# XMOS_chip.net
KiCad netlist of a schematic drawn in Altium Designer
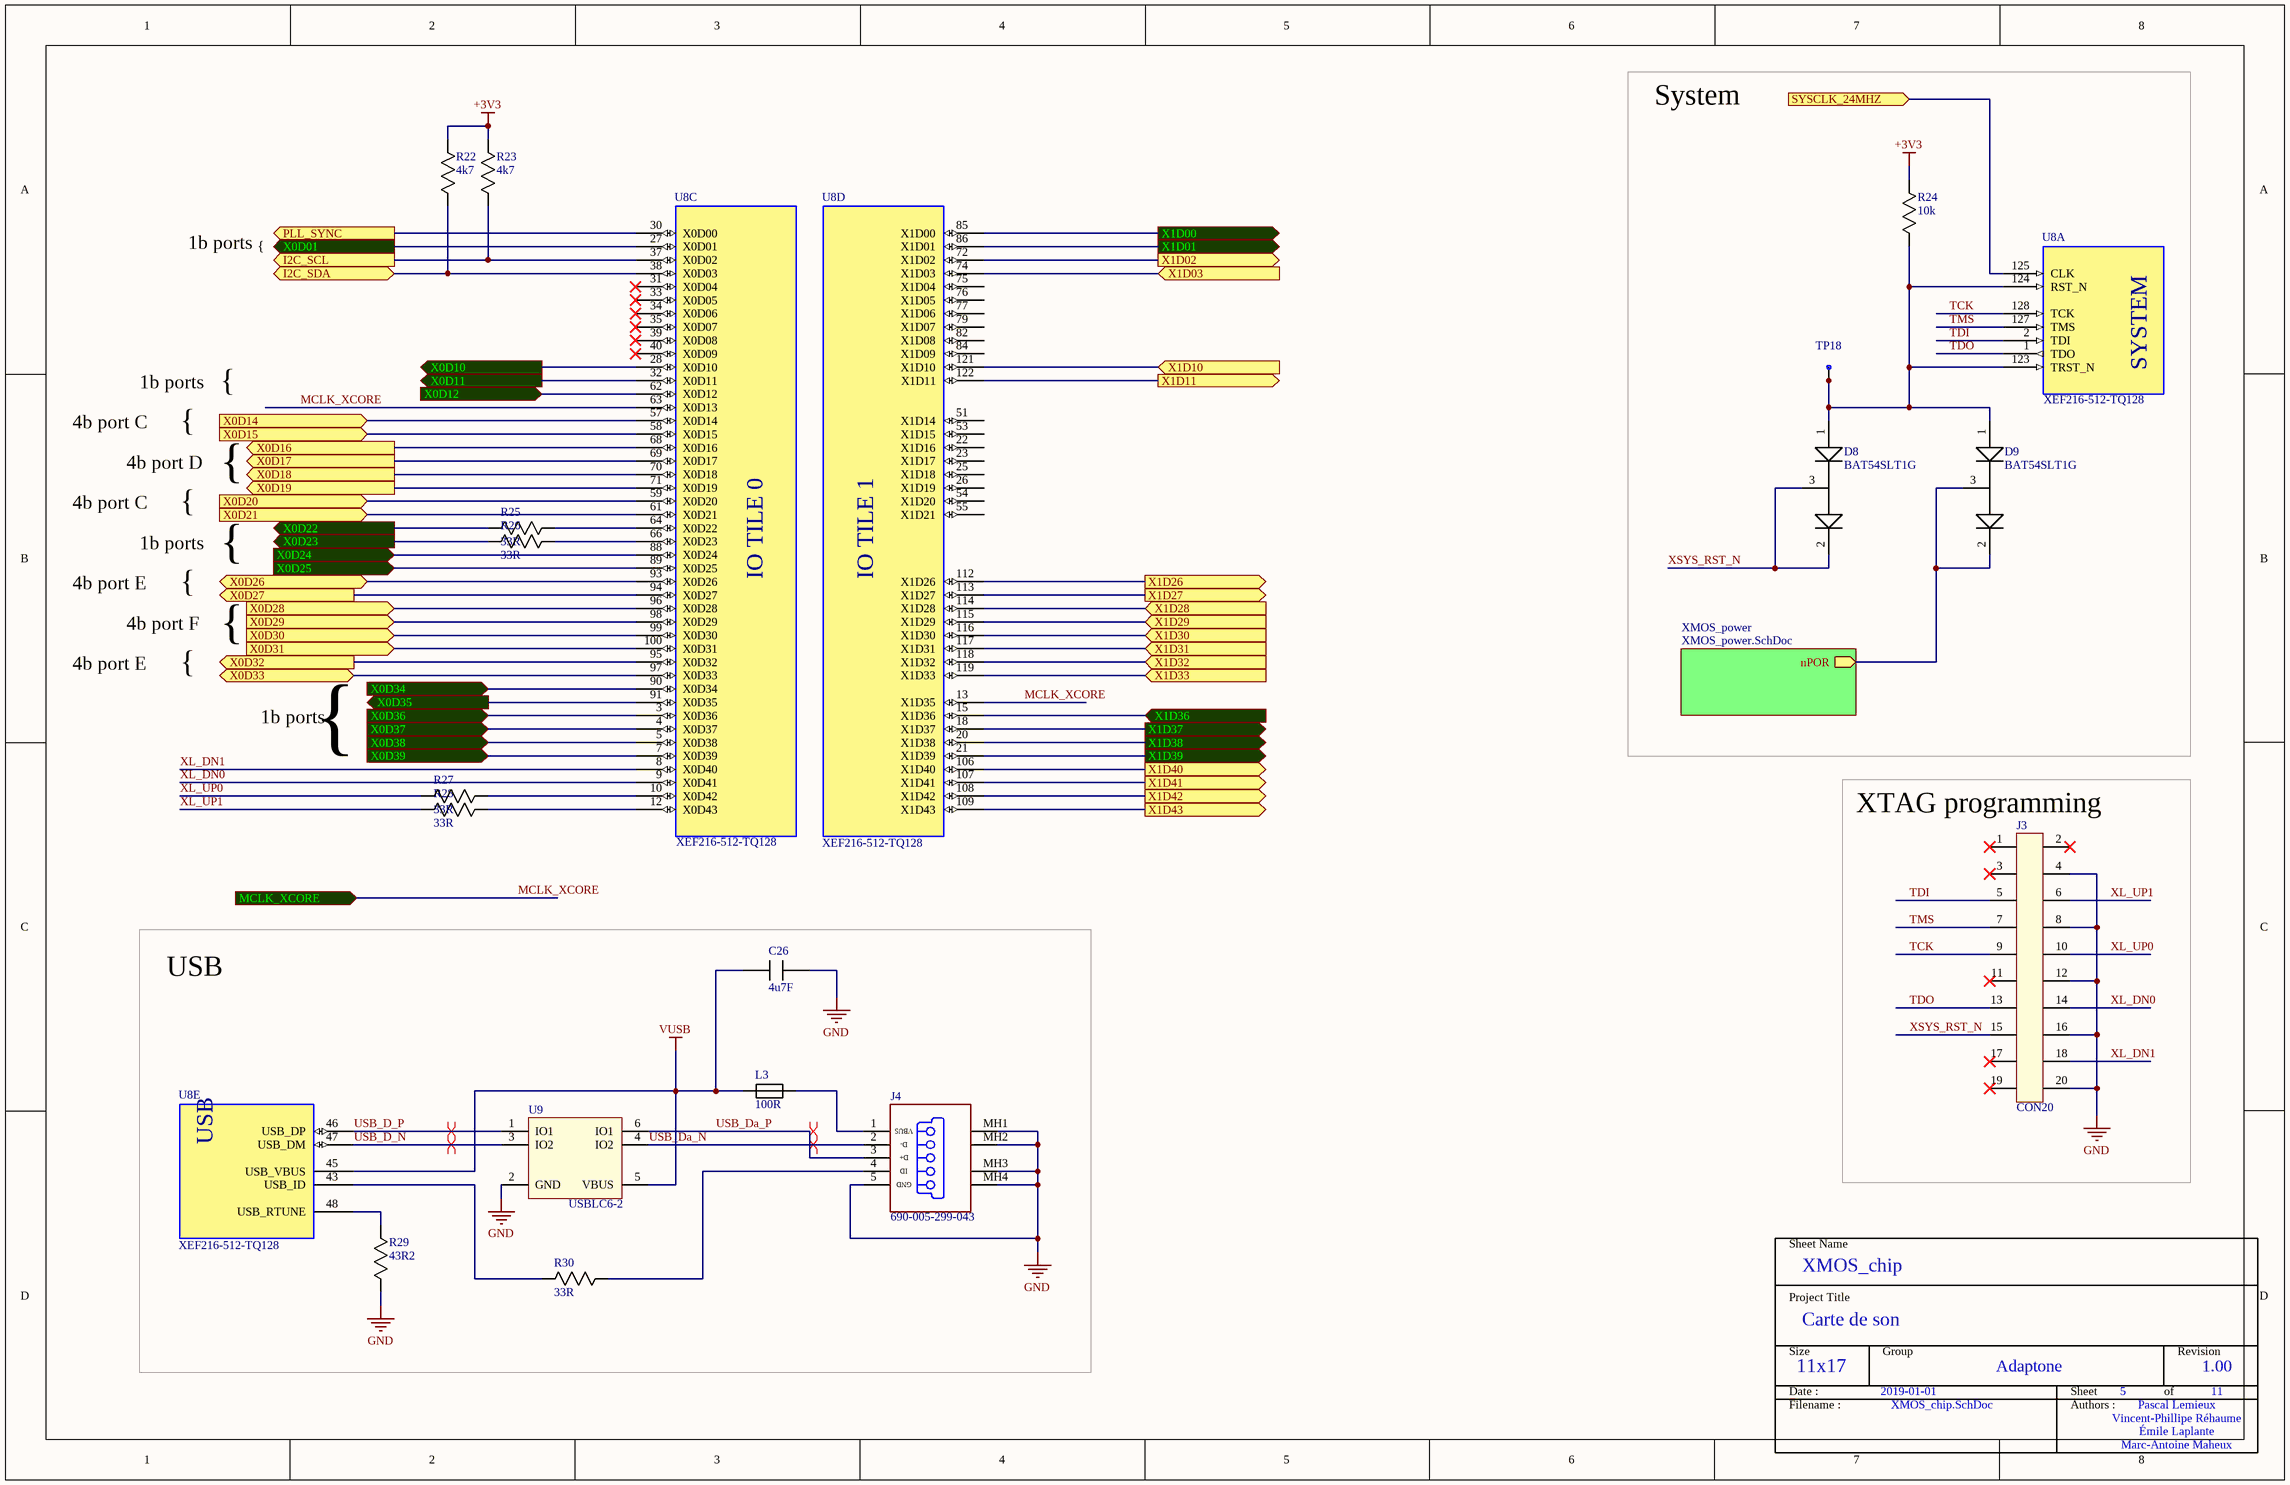
[diagram p0: XMOS_chip.SchDoc]

(export (version "E")
  (design (tool "Eeschema 10.0.6"))
  (components
    (comp (ref "C26")
      (value "4u7F")
      (footprint "0603")
      (description "Capacitor")
      (fields (field (name "MFG") "Samsung"))
      (libsource (lib "ADAPTONE_CARTE_DE_SON") (part "Capacitor"))
    )
    (comp (ref "D8")
      (value "Diode_dual")
      (footprint "SOT23_132")
      (description "Diode")
      (fields (field (name "MFG") "Onsemi") (field (name "MFG_PN") "BAT54SLT1G"))
      (libsource (lib "ADAPTONE_CARTE_DE_SON") (part "Diode_dual"))
    )
    (comp (ref "D9")
      (value "Diode_dual")
      (footprint "SOT23_132")
      (description "Diode")
      (fields (field (name "MFG") "Onsemi") (field (name "MFG_PN") "BAT54SLT1G"))
      (libsource (lib "ADAPTONE_CARTE_DE_SON") (part "Diode_dual"))
    )
    (comp (ref "J3")
      (value "CON20")
      (footprint "CONN20_100mils_pol_SMD")
      (description "20-pins")
      (fields (field (name "MFG") "CNC Tech"))
      (libsource (lib "ADAPTONE_CARTE_DE_SON") (part "CON20"))
    )
    (comp (ref "J4")
      (value "USB_MINIB_690-005-299-043")
      (footprint "CONN_USB_MINIB_690-005-299-043")
      (fields (field (name "MFG") "EDAC") (field (name "MFG_PN") "690-005-299-043"))
      (libsource (lib "ADAPTONE_CARTE_DE_SON") (part "USB_MINIB_690-005-299-043"))
    )
    (comp (ref "L3")
      (value "100R")
      (footprint "0805")
      (description "Ferrite")
      (fields (field (name "MFG") "Bourns"))
      (libsource (lib "ADAPTONE_CARTE_DE_SON") (part "Ferrite"))
    )
    (comp (ref "R22")
      (value "4k7")
      (footprint "0603")
      (description "Resistor")
      (fields (field (name "MFG") "Yageo"))
      (libsource (lib "ADAPTONE_CARTE_DE_SON") (part "Resistor"))
    )
    (comp (ref "R23")
      (value "4k7")
      (footprint "0603")
      (description "Resistor")
      (fields (field (name "MFG") "Yageo"))
      (libsource (lib "ADAPTONE_CARTE_DE_SON") (part "Resistor"))
    )
    (comp (ref "R24")
      (value "10k")
      (footprint "0603")
      (description "Resistor")
      (fields (field (name "MFG") "Yageo"))
      (libsource (lib "ADAPTONE_CARTE_DE_SON") (part "Resistor"))
    )
    (comp (ref "R25")
      (value "33R")
      (footprint "0603")
      (description "Resistor")
      (fields (field (name "MFG") "Yageo"))
      (libsource (lib "ADAPTONE_CARTE_DE_SON") (part "Resistor"))
    )
    (comp (ref "R26")
      (value "33R")
      (footprint "0603")
      (description "Resistor")
      (fields (field (name "MFG") "Yageo"))
      (libsource (lib "ADAPTONE_CARTE_DE_SON") (part "Resistor"))
    )
    (comp (ref "R27")
      (value "33R")
      (footprint "0603")
      (description "Resistor")
      (fields (field (name "MFG") "Yageo"))
      (libsource (lib "ADAPTONE_CARTE_DE_SON") (part "Resistor"))
    )
    (comp (ref "R28")
      (value "33R")
      (footprint "0603")
      (description "Resistor")
      (fields (field (name "MFG") "Yageo"))
      (libsource (lib "ADAPTONE_CARTE_DE_SON") (part "Resistor"))
    )
    (comp (ref "R29")
      (value "43R2")
      (footprint "0603")
      (description "Resistor")
      (fields (field (name "MFG") "Yageo"))
      (libsource (lib "ADAPTONE_CARTE_DE_SON") (part "Resistor"))
    )
    (comp (ref "R30")
      (value "33R")
      (footprint "0603")
      (description "Resistor")
      (fields (field (name "MFG") "Yageo"))
      (libsource (lib "ADAPTONE_CARTE_DE_SON") (part "Resistor"))
    )
    (comp (ref "TP18")
      (value "TESTPOINT")
      (footprint "0603")
      (description "Test point")
      (fields (field (name "MFG") "TE"))
      (libsource (lib "ADAPTONE_CARTE_DE_SON") (part "TESTPOINT"))
    )
    (comp (ref "U8")
      (value "~")
      (footprint "TQFP128_XMOS")
      (description "32-bit multicore microcontroller. 2 Tiles. 16 Logical Cores. 512KB SRAM. 1000MIPS. TQFP128.")
      (fields (field (name "MFG") "XMOS") (field (name "MFG_PN") "XEF216-512-TQ128"))
      (libsource (lib "ADAPTONE_CARTE_DE_SON") (part "XMOS_XEF216-512-TQ128"))
    )
    (comp (ref "U9")
      (value "USBLC6-2")
      (footprint "USBLC6-2")
      (description "USB overvoltage protection")
      (fields (field (name "MFG") "ST") (field (name "MFG_PN") "USBLC6-2"))
      (libsource (lib "ADAPTONE_CARTE_DE_SON") (part "USBLC6-2"))
    )
  )
  (nets
    (net (code "1") (name "+3V3") (class "Default")
      (node (ref "R22") (pin "1") (pintype "passive"))
      (node (ref "R23") (pin "1") (pintype "passive"))
      (node (ref "R24") (pin "1") (pintype "passive"))
    )
    (net (code "2") (name "/I2C_SCL") (class "Default")
      (node (ref "R23") (pin "2") (pintype "passive"))
      (node (ref "U8") (pin "37") (pinfunction "X0D02_37") (pintype "bidirectional"))
    )
    (net (code "3") (name "/I2C_SDA") (class "Default")
      (node (ref "R22") (pin "2") (pintype "passive"))
      (node (ref "U8") (pin "38") (pinfunction "X0D03_38") (pintype "bidirectional"))
    )
    (net (code "4") (name "/MCLK_XCORE") (class "Default")
      (node (ref "U8") (pin "13") (pinfunction "X1D35_13") (pintype "bidirectional"))
      (node (ref "U8") (pin "63") (pinfunction "X0D13_63") (pintype "bidirectional"))
    )
    (net (code "5") (name "/PLL_SYNC") (class "Default")
      (node (ref "U8") (pin "30") (pinfunction "X0D00_30") (pintype "bidirectional"))
    )
    (net (code "6") (name "/SYSCLK_24MHZ") (class "Default")
      (node (ref "U8") (pin "125") (pinfunction "CLK_125") (pintype "input"))
    )
    (net (code "7") (name "/TCK") (class "Default")
      (node (ref "J3") (pin "9") (pinfunction "9_9") (pintype "passive"))
      (node (ref "U8") (pin "128") (pinfunction "TCK_128") (pintype "input"))
    )
    (net (code "8") (name "/TDI") (class "Default")
      (node (ref "J3") (pin "5") (pinfunction "5_5") (pintype "passive"))
      (node (ref "U8") (pin "2") (pinfunction "TDI_2") (pintype "input"))
    )
    (net (code "9") (name "/TDO") (class "Default")
      (node (ref "J3") (pin "13") (pinfunction "13_13") (pintype "passive"))
      (node (ref "U8") (pin "1") (pinfunction "TDO_1") (pintype "output"))
    )
    (net (code "10") (name "/TMS") (class "Default")
      (node (ref "J3") (pin "7") (pinfunction "7_7") (pintype "passive"))
      (node (ref "U8") (pin "127") (pinfunction "TMS_127") (pintype "input"))
    )
    (net (code "11") (name "/USB_D_N") (class "Default")
      (node (ref "U8") (pin "47") (pinfunction "USB_DM_47") (pintype "bidirectional"))
      (node (ref "U9") (pin "3") (pinfunction "IO2_3") (pintype "passive"))
    )
    (net (code "12") (name "/USB_D_P") (class "Default")
      (node (ref "U8") (pin "46") (pinfunction "USB_DP_46") (pintype "bidirectional"))
      (node (ref "U9") (pin "1") (pinfunction "IO1_1") (pintype "passive"))
    )
    (net (code "13") (name "/USB_Da_N") (class "Default")
      (node (ref "J4") (pin "2") (pinfunction "D-_2") (pintype "passive"))
      (node (ref "U9") (pin "4") (pinfunction "IO2_4") (pintype "passive"))
    )
    (net (code "14") (name "/USB_Da_P") (class "Default")
      (node (ref "J4") (pin "3") (pinfunction "D+_3") (pintype "passive"))
      (node (ref "U9") (pin "6") (pinfunction "IO1_6") (pintype "passive"))
    )
    (net (code "15") (name "/X0D01") (class "Default")
      (node (ref "U8") (pin "27") (pinfunction "X0D01_27") (pintype "bidirectional"))
    )
    (net (code "16") (name "/X0D10") (class "Default")
      (node (ref "U8") (pin "28") (pinfunction "X0D10_28") (pintype "bidirectional"))
    )
    (net (code "17") (name "/X0D11") (class "Default")
      (node (ref "U8") (pin "32") (pinfunction "X0D11_32") (pintype "bidirectional"))
    )
    (net (code "18") (name "/X0D12") (class "Default")
      (node (ref "U8") (pin "62") (pinfunction "X0D12_62") (pintype "bidirectional"))
    )
    (net (code "19") (name "/X0D14") (class "Default")
      (node (ref "U8") (pin "57") (pinfunction "X0D14_57") (pintype "bidirectional"))
    )
    (net (code "20") (name "/X0D15") (class "Default")
      (node (ref "U8") (pin "58") (pinfunction "X0D15_58") (pintype "bidirectional"))
    )
    (net (code "21") (name "/X0D16") (class "Default")
      (node (ref "U8") (pin "68") (pinfunction "X0D16_68") (pintype "bidirectional"))
    )
    (net (code "22") (name "/X0D17") (class "Default")
      (node (ref "U8") (pin "69") (pinfunction "X0D17_69") (pintype "bidirectional"))
    )
    (net (code "23") (name "/X0D18") (class "Default")
      (node (ref "U8") (pin "70") (pinfunction "X0D18_70") (pintype "bidirectional"))
    )
    (net (code "24") (name "/X0D19") (class "Default")
      (node (ref "U8") (pin "71") (pinfunction "X0D19_71") (pintype "bidirectional"))
    )
    (net (code "25") (name "/X0D20") (class "Default")
      (node (ref "U8") (pin "59") (pinfunction "X0D20_59") (pintype "bidirectional"))
    )
    (net (code "26") (name "/X0D21") (class "Default")
      (node (ref "U8") (pin "61") (pinfunction "X0D21_61") (pintype "bidirectional"))
    )
    (net (code "27") (name "/X0D22") (class "Default") (node (ref "R25") (pin "1") (pintype "passive")))
    (net (code "28") (name "/X0D23") (class "Default") (node (ref "R26") (pin "1") (pintype "passive")))
    (net (code "29") (name "/X0D24") (class "Default")
      (node (ref "U8") (pin "88") (pinfunction "X0D24_88") (pintype "bidirectional"))
    )
    (net (code "30") (name "/X0D25") (class "Default")
      (node (ref "U8") (pin "89") (pinfunction "X0D25_89") (pintype "bidirectional"))
    )
    (net (code "31") (name "/X0D26") (class "Default")
      (node (ref "U8") (pin "93") (pinfunction "X0D26_93") (pintype "bidirectional"))
    )
    (net (code "32") (name "/X0D27") (class "Default")
      (node (ref "U8") (pin "94") (pinfunction "X0D27_94") (pintype "bidirectional"))
    )
    (net (code "33") (name "/X0D28") (class "Default")
      (node (ref "U8") (pin "96") (pinfunction "X0D28_96") (pintype "bidirectional"))
    )
    (net (code "34") (name "/X0D29") (class "Default")
      (node (ref "U8") (pin "98") (pinfunction "X0D29_98") (pintype "bidirectional"))
    )
    (net (code "35") (name "/X0D30") (class "Default")
      (node (ref "U8") (pin "99") (pinfunction "X0D30_99") (pintype "bidirectional"))
    )
    (net (code "36") (name "/X0D31") (class "Default")
      (node (ref "U8") (pin "100") (pinfunction "X0D31_100") (pintype "bidirectional"))
    )
    (net (code "37") (name "/X0D32") (class "Default")
      (node (ref "U8") (pin "95") (pinfunction "X0D32_95") (pintype "bidirectional"))
    )
    (net (code "38") (name "/X0D33") (class "Default")
      (node (ref "U8") (pin "97") (pinfunction "X0D33_97") (pintype "bidirectional"))
    )
    (net (code "39") (name "/X0D34") (class "Default")
      (node (ref "U8") (pin "90") (pinfunction "X0D34_90") (pintype "bidirectional"))
    )
    (net (code "40") (name "/X0D35") (class "Default")
      (node (ref "U8") (pin "91") (pinfunction "X0D35_91") (pintype "bidirectional"))
    )
    (net (code "41") (name "/X0D36") (class "Default")
      (node (ref "U8") (pin "3") (pinfunction "X0D36_3") (pintype "bidirectional"))
    )
    (net (code "42") (name "/X0D37") (class "Default")
      (node (ref "U8") (pin "4") (pinfunction "X0D37_4") (pintype "bidirectional"))
    )
    (net (code "43") (name "/X0D38") (class "Default")
      (node (ref "U8") (pin "5") (pinfunction "X0D38_5") (pintype "bidirectional"))
    )
    (net (code "44") (name "/X0D39") (class "Default")
      (node (ref "U8") (pin "7") (pinfunction "X0D39_7") (pintype "bidirectional"))
    )
    (net (code "45") (name "/X1D00") (class "Default")
      (node (ref "U8") (pin "85") (pinfunction "X1D00_85") (pintype "bidirectional"))
    )
    (net (code "46") (name "/X1D01") (class "Default")
      (node (ref "U8") (pin "86") (pinfunction "X1D01_86") (pintype "bidirectional"))
    )
    (net (code "47") (name "/X1D02") (class "Default")
      (node (ref "U8") (pin "72") (pinfunction "X1D02_72") (pintype "bidirectional"))
    )
    (net (code "48") (name "/X1D03") (class "Default")
      (node (ref "U8") (pin "74") (pinfunction "X1D03_74") (pintype "bidirectional"))
    )
    (net (code "49") (name "/X1D10") (class "Default")
      (node (ref "U8") (pin "121") (pinfunction "X1D10_121") (pintype "bidirectional"))
    )
    (net (code "50") (name "/X1D11") (class "Default")
      (node (ref "U8") (pin "122") (pinfunction "X1D11_122") (pintype "bidirectional"))
    )
    (net (code "51") (name "/X1D26") (class "Default")
      (node (ref "U8") (pin "112") (pinfunction "X1D26_112") (pintype "bidirectional"))
    )
    (net (code "52") (name "/X1D27") (class "Default")
      (node (ref "U8") (pin "113") (pinfunction "X1D27_113") (pintype "bidirectional"))
    )
    (net (code "53") (name "/X1D28") (class "Default")
      (node (ref "U8") (pin "114") (pinfunction "X1D28_114") (pintype "bidirectional"))
    )
    (net (code "54") (name "/X1D29") (class "Default")
      (node (ref "U8") (pin "115") (pinfunction "X1D29_115") (pintype "bidirectional"))
    )
    (net (code "55") (name "/X1D30") (class "Default")
      (node (ref "U8") (pin "116") (pinfunction "X1D30_116") (pintype "bidirectional"))
    )
    (net (code "56") (name "/X1D31") (class "Default")
      (node (ref "U8") (pin "117") (pinfunction "X1D31_117") (pintype "bidirectional"))
    )
    (net (code "57") (name "/X1D32") (class "Default")
      (node (ref "U8") (pin "118") (pinfunction "X1D32_118") (pintype "bidirectional"))
    )
    (net (code "58") (name "/X1D33") (class "Default")
      (node (ref "U8") (pin "119") (pinfunction "X1D33_119") (pintype "bidirectional"))
    )
    (net (code "59") (name "/X1D36") (class "Default")
      (node (ref "U8") (pin "15") (pinfunction "X1D36_15") (pintype "bidirectional"))
    )
    (net (code "60") (name "/X1D37") (class "Default")
      (node (ref "U8") (pin "18") (pinfunction "X1D37_18") (pintype "bidirectional"))
    )
    (net (code "61") (name "/X1D38") (class "Default")
      (node (ref "U8") (pin "20") (pinfunction "X1D38_20") (pintype "bidirectional"))
    )
    (net (code "62") (name "/X1D39") (class "Default")
      (node (ref "U8") (pin "21") (pinfunction "X1D39_21") (pintype "bidirectional"))
    )
    (net (code "63") (name "/X1D40") (class "Default")
      (node (ref "U8") (pin "106") (pinfunction "X1D40_106") (pintype "bidirectional"))
    )
    (net (code "64") (name "/X1D41") (class "Default")
      (node (ref "U8") (pin "107") (pinfunction "X1D41_107") (pintype "bidirectional"))
    )
    (net (code "65") (name "/X1D42") (class "Default")
      (node (ref "U8") (pin "108") (pinfunction "X1D42_108") (pintype "bidirectional"))
    )
    (net (code "66") (name "/X1D43") (class "Default")
      (node (ref "U8") (pin "109") (pinfunction "X1D43_109") (pintype "bidirectional"))
    )
    (net (code "67") (name "/XL_DN0") (class "Default")
      (node (ref "J3") (pin "14") (pinfunction "14_14") (pintype "passive"))
      (node (ref "U8") (pin "9") (pinfunction "X0D41_9") (pintype "bidirectional"))
    )
    (net (code "68") (name "/XL_DN1") (class "Default")
      (node (ref "J3") (pin "18") (pinfunction "18_18") (pintype "passive"))
      (node (ref "U8") (pin "8") (pinfunction "X0D40_8") (pintype "bidirectional"))
    )
    (net (code "69") (name "/XL_UP0") (class "Default")
      (node (ref "J3") (pin "10") (pinfunction "10_10") (pintype "passive"))
      (node (ref "R27") (pin "1") (pintype "passive"))
    )
    (net (code "70") (name "/XL_UP1") (class "Default")
      (node (ref "J3") (pin "6") (pinfunction "6_6") (pintype "passive"))
      (node (ref "R28") (pin "1") (pintype "passive"))
    )
    (net (code "71") (name "/XSYS_RST_N") (class "Default")
      (node (ref "D8") (pin "2") (pinfunction "K_2") (pintype "passive"))
      (node (ref "D8") (pin "3") (pinfunction "AK_3") (pintype "passive"))
      (node (ref "J3") (pin "15") (pinfunction "15_15") (pintype "passive"))
    )
    (net (code "72") (name "/nPOR") (class "Default")
      (node (ref "D9") (pin "2") (pinfunction "K_2") (pintype "passive"))
      (node (ref "D9") (pin "3") (pinfunction "AK_3") (pintype "passive"))
    )
    (net (code "73") (name "GND") (class "Default")
      (node (ref "C26") (pin "2") (pintype "passive"))
      (node (ref "J3") (pin "12") (pinfunction "12_12") (pintype "passive"))
      (node (ref "J3") (pin "16") (pinfunction "16_16") (pintype "passive"))
      (node (ref "J3") (pin "20") (pinfunction "20_20") (pintype "passive"))
      (node (ref "J3") (pin "4") (pintype "passive"))
      (node (ref "J3") (pin "8") (pinfunction "8_8") (pintype "passive"))
      (node (ref "J4") (pin "5") (pinfunction "GND_5") (pintype "passive"))
      (node (ref "J4") (pin "MH1") (pinfunction "Tab_MH1") (pintype "passive"))
      (node (ref "J4") (pin "MH2") (pinfunction "Tab_MH2") (pintype "passive"))
      (node (ref "J4") (pin "MH3") (pinfunction "Tab_MH3") (pintype "passive"))
      (node (ref "J4") (pin "MH4") (pinfunction "Tab_MH4") (pintype "passive"))
      (node (ref "R29") (pin "1") (pintype "passive"))
      (node (ref "U9") (pin "2") (pinfunction "GND_2") (pintype "passive"))
    )
    (net (code "74") (name "Net-(J4-NC)") (class "Default")
      (node (ref "J4") (pin "4") (pinfunction "NC_4") (pintype "passive"))
      (node (ref "R30") (pin "1") (pintype "passive"))
    )
    (net (code "75") (name "Net-(J4-V_BUS_(5V))") (class "Default")
      (node (ref "J4") (pin "1") (pinfunction "V_BUS_(5V)_1") (pintype "passive"))
      (node (ref "L3") (pin "2") (pintype "passive"))
    )
    (net (code "76") (name "Net-(U8A-RST_N)") (class "Default")
      (node (ref "D8") (pin "1") (pinfunction "K_1") (pintype "passive"))
      (node (ref "D9") (pin "1") (pinfunction "K_1") (pintype "passive"))
      (node (ref "R24") (pin "2") (pintype "passive"))
      (node (ref "TP18") (pin "1") (pintype "passive"))
      (node (ref "TP18") (pin "2") (pintype "passive"))
      (node (ref "U8") (pin "123") (pinfunction "TRST_N_123") (pintype "input"))
      (node (ref "U8") (pin "124") (pinfunction "RST_N_124") (pintype "input"))
    )
    (net (code "77") (name "Net-(U8C-X0D22)") (class "Default")
      (node (ref "R25") (pin "2") (pintype "passive"))
      (node (ref "U8") (pin "64") (pinfunction "X0D22_64") (pintype "bidirectional"))
    )
    (net (code "78") (name "Net-(U8C-X0D23)") (class "Default")
      (node (ref "R26") (pin "2") (pintype "passive"))
      (node (ref "U8") (pin "66") (pinfunction "X0D23_66") (pintype "bidirectional"))
    )
    (net (code "79") (name "Net-(U8C-X0D42)") (class "Default")
      (node (ref "R27") (pin "2") (pintype "passive"))
      (node (ref "U8") (pin "10") (pinfunction "X0D42_10") (pintype "bidirectional"))
    )
    (net (code "80") (name "Net-(U8C-X0D43)") (class "Default")
      (node (ref "R28") (pin "2") (pintype "passive"))
      (node (ref "U8") (pin "12") (pinfunction "X0D43_12") (pintype "bidirectional"))
    )
    (net (code "81") (name "Net-(U8E-USB_ID)") (class "Default")
      (node (ref "R30") (pin "2") (pintype "passive"))
      (node (ref "U8") (pin "43") (pinfunction "USB_ID_43") (pintype "passive"))
    )
    (net (code "82") (name "Net-(U8E-USB_RTUNE)") (class "Default")
      (node (ref "R29") (pin "2") (pintype "passive"))
      (node (ref "U8") (pin "48") (pinfunction "USB_RTUNE_48") (pintype "passive"))
    )
    (net (code "83") (name "VUSB") (class "Default")
      (node (ref "C26") (pin "1") (pintype "passive"))
      (node (ref "L3") (pin "1") (pintype "passive"))
      (node (ref "U8") (pin "45") (pinfunction "USB_VBUS_45") (pintype "passive"))
      (node (ref "U9") (pin "5") (pinfunction "VBUS_5") (pintype "passive"))
    )
    (net (code "84") (name "unconnected-(J3-Pad1)") (class "Default")
      (node (ref "J3") (pin "1") (pintype "passive+no_connect"))
    )
    (net (code "85") (name "unconnected-(J3-Pad2)") (class "Default")
      (node (ref "J3") (pin "2") (pintype "passive+no_connect"))
    )
    (net (code "86") (name "unconnected-(J3-Pad3)") (class "Default")
      (node (ref "J3") (pin "3") (pintype "passive+no_connect"))
    )
    (net (code "87") (name "unconnected-(J3-Pad11)") (class "Default")
      (node (ref "J3") (pin "11") (pinfunction "11_11") (pintype "passive+no_connect"))
    )
    (net (code "88") (name "unconnected-(J3-Pad17)") (class "Default")
      (node (ref "J3") (pin "17") (pinfunction "17_17") (pintype "passive+no_connect"))
    )
    (net (code "89") (name "unconnected-(J3-Pad19)") (class "Default")
      (node (ref "J3") (pin "19") (pinfunction "19_19") (pintype "passive+no_connect"))
    )
    (net (code "90") (name "unconnected-(U8C-X0D04-Pad31)") (class "Default")
      (node (ref "U8") (pin "31") (pinfunction "X0D04_31") (pintype "bidirectional+no_connect"))
    )
    (net (code "91") (name "unconnected-(U8C-X0D05-Pad33)") (class "Default")
      (node (ref "U8") (pin "33") (pinfunction "X0D05_33") (pintype "bidirectional+no_connect"))
    )
    (net (code "92") (name "unconnected-(U8C-X0D06-Pad34)") (class "Default")
      (node (ref "U8") (pin "34") (pinfunction "X0D06_34") (pintype "bidirectional+no_connect"))
    )
    (net (code "93") (name "unconnected-(U8C-X0D07-Pad35)") (class "Default")
      (node (ref "U8") (pin "35") (pinfunction "X0D07_35") (pintype "bidirectional+no_connect"))
    )
    (net (code "94") (name "unconnected-(U8C-X0D08-Pad39)") (class "Default")
      (node (ref "U8") (pin "39") (pinfunction "X0D08_39") (pintype "bidirectional+no_connect"))
    )
    (net (code "95") (name "unconnected-(U8C-X0D09-Pad40)") (class "Default")
      (node (ref "U8") (pin "40") (pinfunction "X0D09_40") (pintype "bidirectional+no_connect"))
    )
    (net (code "96") (name "unconnected-(U8D-X1D04-Pad75)") (class "Default")
      (node (ref "U8") (pin "75") (pinfunction "X1D04_75") (pintype "bidirectional"))
    )
    (net (code "97") (name "unconnected-(U8D-X1D05-Pad76)") (class "Default")
      (node (ref "U8") (pin "76") (pinfunction "X1D05_76") (pintype "bidirectional"))
    )
    (net (code "98") (name "unconnected-(U8D-X1D06-Pad77)") (class "Default")
      (node (ref "U8") (pin "77") (pinfunction "X1D06_77") (pintype "bidirectional"))
    )
    (net (code "99") (name "unconnected-(U8D-X1D07-Pad79)") (class "Default")
      (node (ref "U8") (pin "79") (pinfunction "X1D07_79") (pintype "bidirectional"))
    )
    (net (code "100") (name "unconnected-(U8D-X1D08-Pad82)") (class "Default")
      (node (ref "U8") (pin "82") (pinfunction "X1D08_82") (pintype "bidirectional"))
    )
    (net (code "101") (name "unconnected-(U8D-X1D09-Pad84)") (class "Default")
      (node (ref "U8") (pin "84") (pinfunction "X1D09_84") (pintype "bidirectional"))
    )
    (net (code "102") (name "unconnected-(U8D-X1D14-Pad51)") (class "Default")
      (node (ref "U8") (pin "51") (pinfunction "X1D14_51") (pintype "bidirectional"))
    )
    (net (code "103") (name "unconnected-(U8D-X1D15-Pad53)") (class "Default")
      (node (ref "U8") (pin "53") (pinfunction "X1D15_53") (pintype "bidirectional"))
    )
    (net (code "104") (name "unconnected-(U8D-X1D16-Pad22)") (class "Default")
      (node (ref "U8") (pin "22") (pinfunction "X1D16_22") (pintype "bidirectional"))
    )
    (net (code "105") (name "unconnected-(U8D-X1D17-Pad23)") (class "Default")
      (node (ref "U8") (pin "23") (pinfunction "X1D17_23") (pintype "bidirectional"))
    )
    (net (code "106") (name "unconnected-(U8D-X1D18-Pad25)") (class "Default")
      (node (ref "U8") (pin "25") (pinfunction "X1D18_25") (pintype "bidirectional"))
    )
    (net (code "107") (name "unconnected-(U8D-X1D19-Pad26)") (class "Default")
      (node (ref "U8") (pin "26") (pinfunction "X1D19_26") (pintype "bidirectional"))
    )
    (net (code "108") (name "unconnected-(U8D-X1D20-Pad54)") (class "Default")
      (node (ref "U8") (pin "54") (pinfunction "X1D20_54") (pintype "bidirectional"))
    )
    (net (code "109") (name "unconnected-(U8D-X1D21-Pad55)") (class "Default")
      (node (ref "U8") (pin "55") (pinfunction "X1D21_55") (pintype "bidirectional"))
    )
  )
)
